# Conn_pcb3.net
KiCad netlist of a schematic drawn in EAGLE
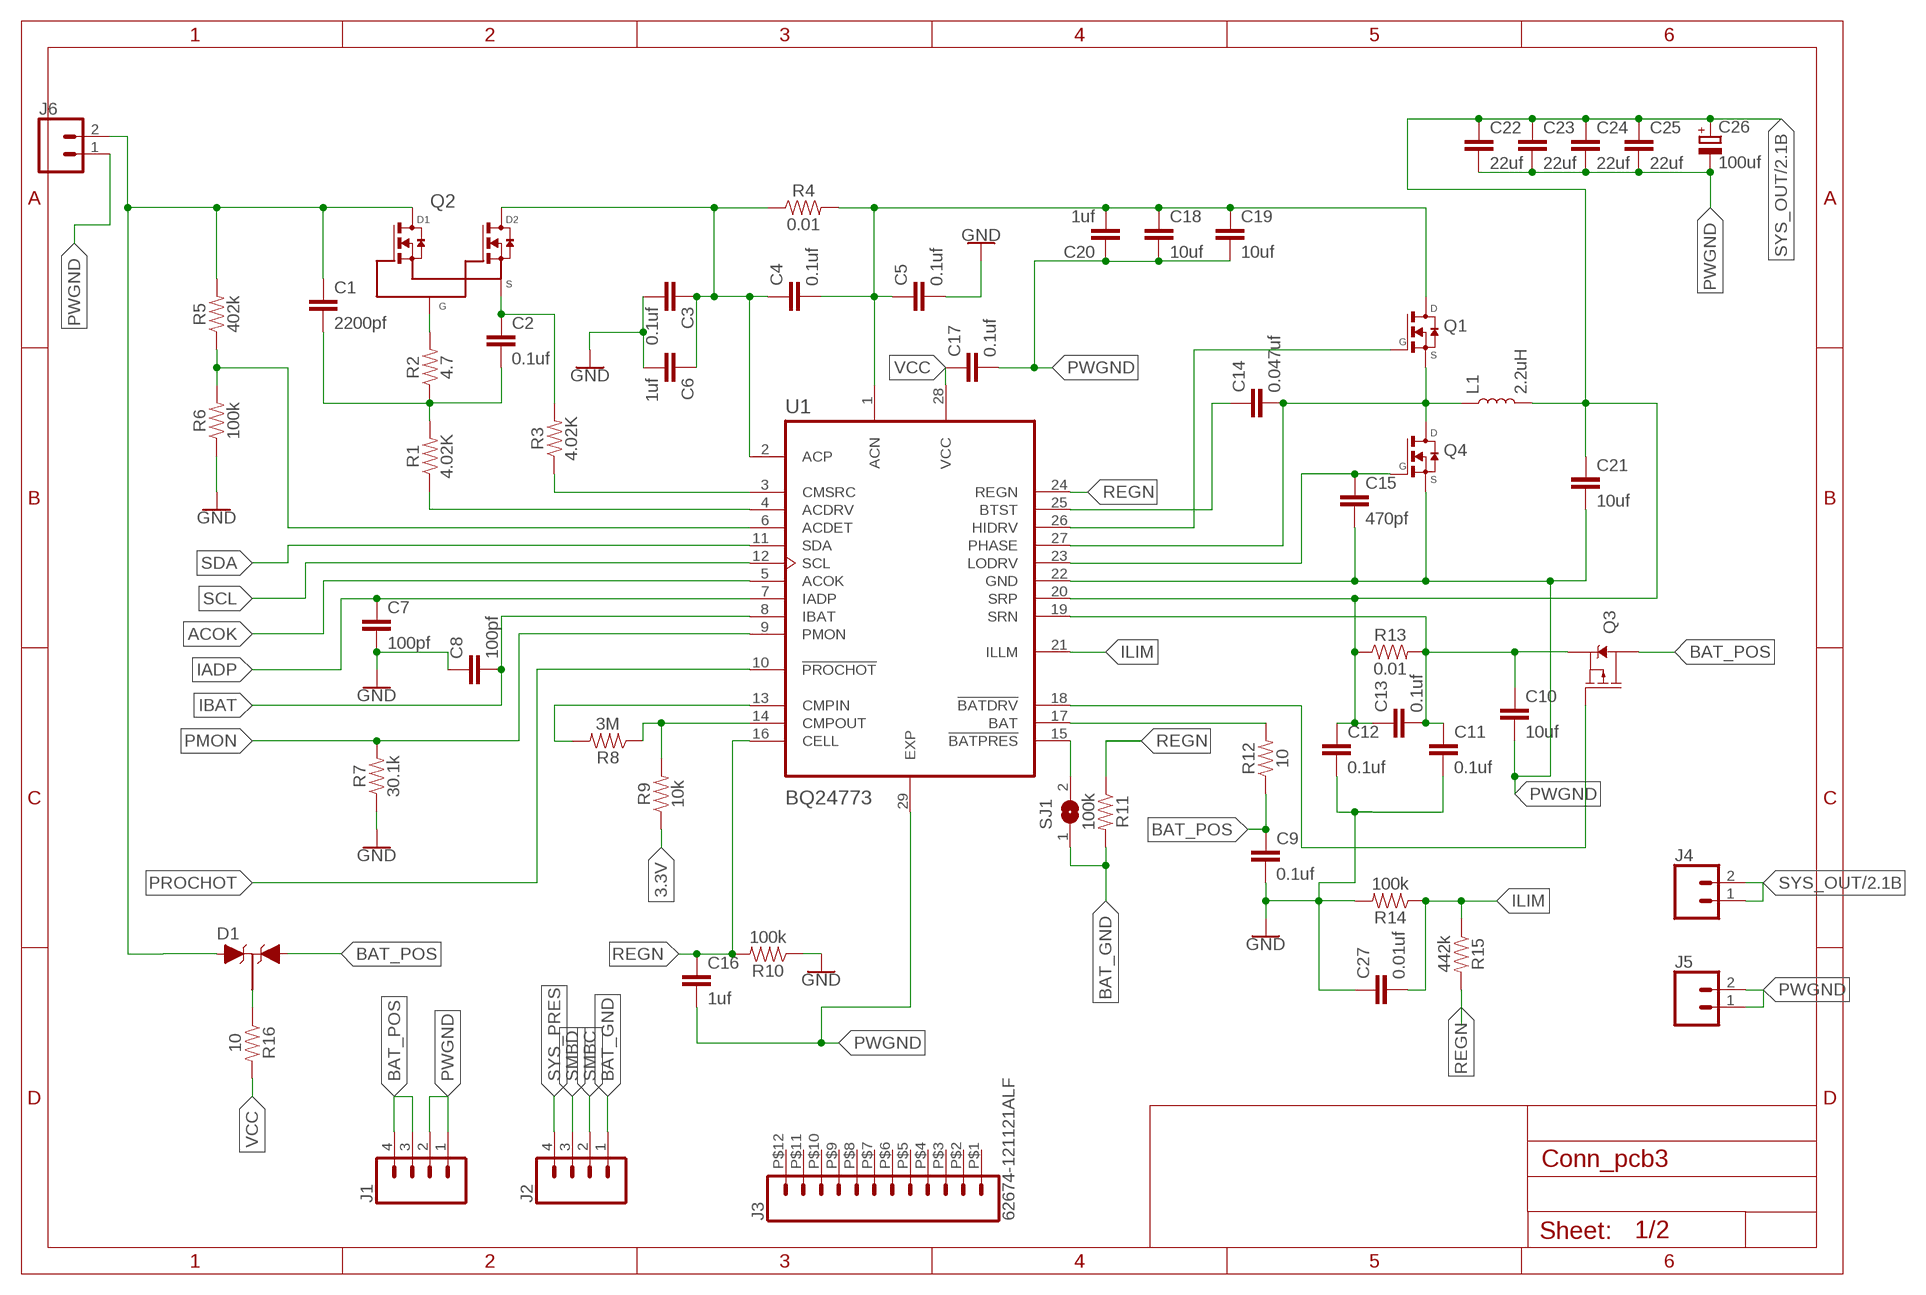
[diagram p0: schematic, sheet 1]
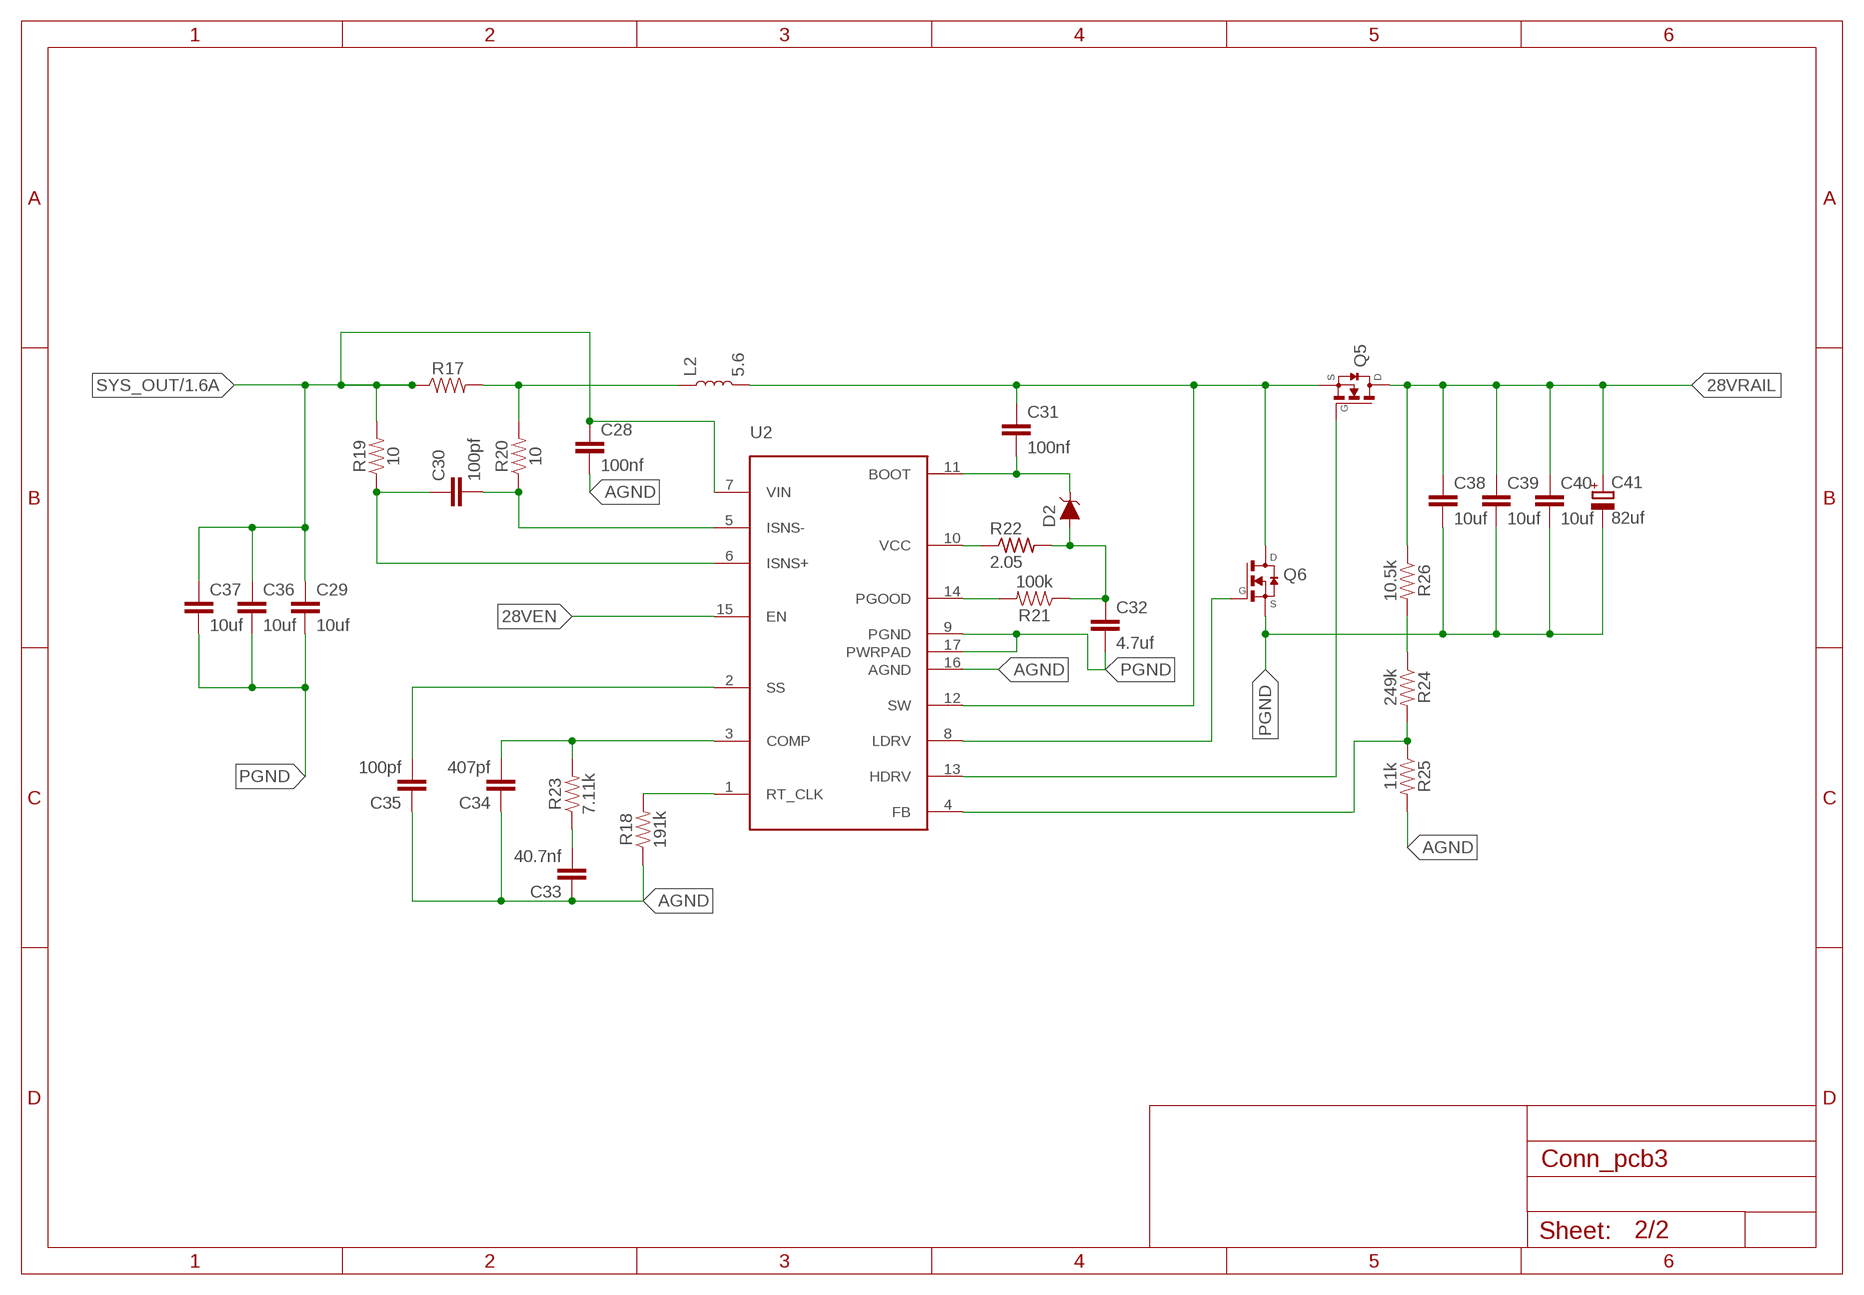
[diagram p1: schematic, sheet 2]

(export (version "E")
  (design (tool "Eeschema 10.0.6"))
  (components
    (comp (ref "C1")
      (value "2200pf")
      (footprint "eagle-import:CAPC1005X50")
      (libsource (lib "eagle-import") (part "CAP0402"))
    )
    (comp (ref "C2")
      (value "0.1uf")
      (footprint "eagle-import:CAPC1005X50")
      (libsource (lib "eagle-import") (part "CAP0402"))
    )
    (comp (ref "C3")
      (value "0.1uf")
      (footprint "eagle-import:CAPC1005X50")
      (libsource (lib "eagle-import") (part "CAP0402"))
    )
    (comp (ref "C4")
      (value "0.1uf")
      (footprint "eagle-import:CAPC1005X50")
      (libsource (lib "eagle-import") (part "CAP0402"))
    )
    (comp (ref "C5")
      (value "0.1uf")
      (footprint "eagle-import:CAPC1005X50")
      (libsource (lib "eagle-import") (part "CAP0402"))
    )
    (comp (ref "C6")
      (value "1uf")
      (footprint "eagle-import:CAPC1005X50")
      (libsource (lib "eagle-import") (part "CAP0402"))
    )
    (comp (ref "C7")
      (value "100pf")
      (footprint "eagle-import:CAPC1005X50")
      (libsource (lib "eagle-import") (part "CAP0402"))
    )
    (comp (ref "C8")
      (value "100pf")
      (footprint "eagle-import:CAPC1005X50")
      (libsource (lib "eagle-import") (part "CAP0402"))
    )
    (comp (ref "C9")
      (value "0.1uf")
      (footprint "eagle-import:CAPC1005X50")
      (libsource (lib "eagle-import") (part "CAP0402"))
    )
    (comp (ref "C10")
      (value "10uf")
      (footprint "eagle-import:C0805K")
      (libsource (lib "eagle-import") (part "C-EUC0805K"))
    )
    (comp (ref "C11")
      (value "0.1uf")
      (footprint "eagle-import:CAPC1005X50")
      (libsource (lib "eagle-import") (part "CAP0402"))
    )
    (comp (ref "C12")
      (value "0.1uf")
      (footprint "eagle-import:CAPC1005X50")
      (libsource (lib "eagle-import") (part "CAP0402"))
    )
    (comp (ref "C13")
      (value "0.1uf")
      (footprint "eagle-import:CAPC1005X50")
      (libsource (lib "eagle-import") (part "CAP0402"))
    )
    (comp (ref "C14")
      (value "0.047uf")
      (footprint "eagle-import:CAPC1005X50")
      (libsource (lib "eagle-import") (part "CAP0402"))
    )
    (comp (ref "C15")
      (value "470pf")
      (footprint "eagle-import:CAPC1005X50")
      (libsource (lib "eagle-import") (part "CAP0402"))
    )
    (comp (ref "C16")
      (value "1uf")
      (footprint "eagle-import:CAPC1005X50")
      (libsource (lib "eagle-import") (part "CAP0402"))
    )
    (comp (ref "C17")
      (value "0.1uf")
      (footprint "eagle-import:CAPC1005X50")
      (libsource (lib "eagle-import") (part "CAP0402"))
    )
    (comp (ref "C18")
      (value "10uf")
      (footprint "eagle-import:C0805K")
      (libsource (lib "eagle-import") (part "C-EUC0805K"))
    )
    (comp (ref "C19")
      (value "10uf")
      (footprint "eagle-import:C0805K")
      (libsource (lib "eagle-import") (part "C-EUC0805K"))
    )
    (comp (ref "C20")
      (value "1uf")
      (footprint "eagle-import:CAPC1005X50")
      (libsource (lib "eagle-import") (part "CAP0402"))
    )
    (comp (ref "C21")
      (value "10uf")
      (footprint "eagle-import:C0805K")
      (libsource (lib "eagle-import") (part "C-EUC0805K"))
    )
    (comp (ref "C22")
      (value "22uf")
      (footprint "eagle-import:C1206")
      (libsource (lib "eagle-import") (part "C-EUC1206"))
    )
    (comp (ref "C23")
      (value "22uf")
      (footprint "eagle-import:C1206")
      (libsource (lib "eagle-import") (part "C-EUC1206"))
    )
    (comp (ref "C24")
      (value "22uf")
      (footprint "eagle-import:C1206")
      (libsource (lib "eagle-import") (part "C-EUC1206"))
    )
    (comp (ref "C25")
      (value "22uf")
      (footprint "eagle-import:C1206")
      (libsource (lib "eagle-import") (part "C-EUC1206"))
    )
    (comp (ref "C26")
      (value "100uf")
      (footprint "eagle-import:CAPAE1030X800")
      (libsource (lib "eagle-import") (part "16SVP100M"))
    )
    (comp (ref "C27")
      (value "0.01uf")
      (footprint "eagle-import:CAPC1005X50")
      (libsource (lib "eagle-import") (part "CAP0402"))
    )
    (comp (ref "D1")
      (value "BAT54C-7-F")
      (footprint "eagle-import:SOT95P235X110-3")
      (libsource (lib "eagle-import") (part "BAT54C-7-F"))
    )
    (comp (ref "J1")
      (value "CONN_041.3")
      (footprint "eagle-import:1X04_NO_SILK_1.3")
      (libsource (lib "eagle-import") (part "CONN_041.3"))
    )
    (comp (ref "J2")
      (value "CONN_041.3")
      (footprint "eagle-import:1X04_NO_SILK_1.3")
      (libsource (lib "eagle-import") (part "CONN_041.3"))
    )
    (comp (ref "J3")
      (value "62674-121121ALF")
      (footprint "eagle-import:62674-121121ALF")
      (libsource (lib "eagle-import") (part "62674-121121ALF"))
    )
    (comp (ref "J4")
      (value "CONN_021.4HOLE")
      (footprint "eagle-import:1X02_1.4HOLE")
      (libsource (lib "eagle-import") (part "CONN_021.4HOLE"))
    )
    (comp (ref "J5")
      (value "CONN_021.4HOLE")
      (footprint "eagle-import:1X02_1.4HOLE")
      (libsource (lib "eagle-import") (part "CONN_021.4HOLE"))
    )
    (comp (ref "J6")
      (value "CONN_021.4HOLE")
      (footprint "eagle-import:1X02_1.4HOLE")
      (libsource (lib "eagle-import") (part "CONN_021.4HOLE"))
    )
    (comp (ref "L1")
      (value "2.2uH")
      (footprint "eagle-import:RESM6365X610")
      (libsource (lib "eagle-import") (part "XEL6060-222MEB"))
    )
    (comp (ref "Q1")
      (value "CSD17308Q3")
      (footprint "eagle-import:SON65P330X330X110-8")
      (fields (field (name "SPICEPREFIX") "Q"))
      (libsource (lib "eagle-import") (part "CSD17308Q3"))
    )
    (comp (ref "Q2")
      (value "CSD87312Q3EVSON")
      (footprint "eagle-import:QFN65P330X330X100-12")
      (libsource (lib "eagle-import") (part "CSD87312Q3EVSON"))
    )
    (comp (ref "Q3")
      (value "CSD25402Q3A")
      (footprint "eagle-import:CSD25402Q3A")
      (libsource (lib "eagle-import") (part "CSD25402Q3A"))
    )
    (comp (ref "Q4")
      (value "CSD17308Q3")
      (footprint "eagle-import:SON65P330X330X110-8")
      (fields (field (name "SPICEPREFIX") "Q"))
      (libsource (lib "eagle-import") (part "CSD17308Q3"))
    )
    (comp (ref "R1")
      (value "4.02K")
      (footprint "eagle-import:0402")
      (libsource (lib "eagle-import") (part "RES4K04020402"))
    )
    (comp (ref "R2")
      (value "4.7")
      (footprint "eagle-import:0402")
      (libsource (lib "eagle-import") (part "RES4K04020402"))
    )
    (comp (ref "R3")
      (value "4.02K")
      (footprint "eagle-import:0402")
      (libsource (lib "eagle-import") (part "RES4K04020402"))
    )
    (comp (ref "R4")
      (value "0.01")
      (footprint "eagle-import:1206")
      (libsource (lib "eagle-import") (part "SENSE-RES"))
    )
    (comp (ref "R5")
      (value "402k")
      (footprint "eagle-import:0402")
      (libsource (lib "eagle-import") (part "RES4K04020402"))
    )
    (comp (ref "R6")
      (value "100k")
      (footprint "eagle-import:0402")
      (libsource (lib "eagle-import") (part "RES4K04020402"))
    )
    (comp (ref "R7")
      (value "30.1k")
      (footprint "eagle-import:0402")
      (libsource (lib "eagle-import") (part "RES4K04020402"))
    )
    (comp (ref "R8")
      (value "3M")
      (footprint "eagle-import:0402")
      (libsource (lib "eagle-import") (part "RES4K04020402"))
    )
    (comp (ref "R9")
      (value "10k")
      (footprint "eagle-import:0402")
      (libsource (lib "eagle-import") (part "RES4K04020402"))
    )
    (comp (ref "R10")
      (value "100k")
      (footprint "eagle-import:0402")
      (libsource (lib "eagle-import") (part "RES4K04020402"))
    )
    (comp (ref "R11")
      (value "100k")
      (footprint "eagle-import:0402")
      (libsource (lib "eagle-import") (part "RES4K04020402"))
    )
    (comp (ref "R12")
      (value "10")
      (footprint "eagle-import:0402")
      (libsource (lib "eagle-import") (part "RES4K04020402"))
    )
    (comp (ref "R13")
      (value "0.01")
      (footprint "eagle-import:1206")
      (libsource (lib "eagle-import") (part "SENSE-RES"))
    )
    (comp (ref "R14")
      (value "100k")
      (footprint "eagle-import:0402")
      (libsource (lib "eagle-import") (part "RES4K04020402"))
    )
    (comp (ref "R15")
      (value "442k")
      (footprint "eagle-import:0402")
      (libsource (lib "eagle-import") (part "RES4K04020402"))
    )
    (comp (ref "R16")
      (value "10")
      (footprint "eagle-import:0402")
      (libsource (lib "eagle-import") (part "RES4K04020402"))
    )
    (comp (ref "SJ1") (value "SJ") (footprint "eagle-import:SJ") (libsource (lib "eagle-import") (part "SJ")))
    (comp (ref "U1")
      (value "BQ24773")
      (footprint "eagle-import:QFN40P400X400X80-29T240")
      (libsource (lib "eagle-import") (part "BQ24773"))
    )
    (comp (ref "C28")
      (value "100nf")
      (footprint "eagle-import:C0402K")
      (libsource (lib "eagle-import") (part "C-EUC0402K"))
    )
    (comp (ref "C29")
      (value "10uf")
      (footprint "eagle-import:C0805K")
      (libsource (lib "eagle-import") (part "C-EUC0805K"))
    )
    (comp (ref "C30")
      (value "100pf")
      (footprint "eagle-import:C0402K")
      (libsource (lib "eagle-import") (part "C-EUC0402K"))
    )
    (comp (ref "C31")
      (value "100nf")
      (footprint "eagle-import:C0402K")
      (libsource (lib "eagle-import") (part "C-EUC0402K"))
    )
    (comp (ref "C32")
      (value "4.7uf")
      (footprint "eagle-import:C0402K")
      (libsource (lib "eagle-import") (part "C-EUC0402K"))
    )
    (comp (ref "C33")
      (value "40.7nf")
      (footprint "eagle-import:C0402K")
      (libsource (lib "eagle-import") (part "C-EUC0402K"))
    )
    (comp (ref "C34")
      (value "407pf")
      (footprint "eagle-import:C0402K")
      (libsource (lib "eagle-import") (part "C-EUC0402K"))
    )
    (comp (ref "C35")
      (value "100pf")
      (footprint "eagle-import:C0402K")
      (libsource (lib "eagle-import") (part "C-EUC0402K"))
    )
    (comp (ref "C36")
      (value "10uf")
      (footprint "eagle-import:C0805K")
      (libsource (lib "eagle-import") (part "C-EUC0805K"))
    )
    (comp (ref "C37")
      (value "10uf")
      (footprint "eagle-import:C0805K")
      (libsource (lib "eagle-import") (part "C-EUC0805K"))
    )
    (comp (ref "C38")
      (value "10uf")
      (footprint "eagle-import:C0805K")
      (libsource (lib "eagle-import") (part "C-EUC0805K"))
    )
    (comp (ref "C39")
      (value "10uf")
      (footprint "eagle-import:C0805K")
      (libsource (lib "eagle-import") (part "C-EUC0805K"))
    )
    (comp (ref "C40")
      (value "10uf")
      (footprint "eagle-import:C0805K")
      (libsource (lib "eagle-import") (part "C-EUC0805K"))
    )
    (comp (ref "C41")
      (value "82uf")
      (footprint "eagle-import:CAPAE830X1040")
      (libsource (lib "eagle-import") (part "PCR1H820MCL6GS"))
    )
    (comp (ref "D2")
      (value "SS24FL")
      (footprint "eagle-import:SODFL3617X108")
      (libsource (lib "eagle-import") (part "SS24FL"))
    )
    (comp (ref "L2")
      (value "5.6")
      (footprint "eagle-import:RESM7275X700")
      (libsource (lib "eagle-import") (part "XAL7070-472MEB"))
    )
    (comp (ref "Q5")
      (value "SIS184DN-T1-GE3")
      (footprint "eagle-import:SIS184DN-T1-GE3")
      (libsource (lib "eagle-import") (part "SIS184DN-T1-GE3"))
    )
    (comp (ref "Q6")
      (value "SIS184DN-T1-GE3")
      (footprint "eagle-import:SIS184DN-T1-GE3")
      (libsource (lib "eagle-import") (part "SIS184DN-T1-GE3"))
    )
    (comp (ref "R17")
      (value "LRMAM2512-R0035FT4")
      (footprint "eagle-import:RESC6432X90")
      (libsource (lib "eagle-import") (part "LRMAM2512-R0035FT4"))
    )
    (comp (ref "R18")
      (value "191k")
      (footprint "eagle-import:0402")
      (libsource (lib "eagle-import") (part "RES4K04020402"))
    )
    (comp (ref "R19")
      (value "10")
      (footprint "eagle-import:0402")
      (libsource (lib "eagle-import") (part "RES4K04020402"))
    )
    (comp (ref "R20")
      (value "10")
      (footprint "eagle-import:0402")
      (libsource (lib "eagle-import") (part "RES4K04020402"))
    )
    (comp (ref "R21")
      (value "100k")
      (footprint "eagle-import:0402")
      (libsource (lib "eagle-import") (part "RES4K04020402"))
    )
    (comp (ref "R22")
      (value "2.05")
      (footprint "eagle-import:R0603")
      (libsource (lib "eagle-import") (part "R-US_R0603"))
    )
    (comp (ref "R23")
      (value "7.11k")
      (footprint "eagle-import:0402")
      (libsource (lib "eagle-import") (part "RES4K04020402"))
    )
    (comp (ref "R24")
      (value "249k")
      (footprint "eagle-import:0402")
      (libsource (lib "eagle-import") (part "RES4K04020402"))
    )
    (comp (ref "R25")
      (value "11k")
      (footprint "eagle-import:0402")
      (libsource (lib "eagle-import") (part "RES4K04020402"))
    )
    (comp (ref "R26")
      (value "10.5k")
      (footprint "eagle-import:0402")
      (libsource (lib "eagle-import") (part "RES4K04020402"))
    )
    (comp (ref "U2")
      (value "TPS43061")
      (footprint "eagle-import:QFN50P300X300X100-17T80X120")
      (libsource (lib "eagle-import") (part "TPS43061"))
    )
  )
  (nets
    (net (code "1") (name "3.3V") (class "Default")
      (node (ref "R9") (pin "1") (pinfunction "1_1") (pintype "passive"))
    )
    (net (code "2") (name "28VEN") (class "Default")
      (node (ref "U2") (pin "15") (pinfunction "EN_15") (pintype "bidirectional"))
    )
    (net (code "3") (name "28VRAIL") (class "Default")
      (node (ref "C38") (pin "1") (pinfunction "1_1") (pintype "passive"))
      (node (ref "C39") (pin "1") (pinfunction "1_1") (pintype "passive"))
      (node (ref "C40") (pin "1") (pinfunction "1_1") (pintype "passive"))
      (node (ref "C41") (pin "1") (pinfunction "+_1") (pintype "passive"))
      (node (ref "Q5") (pin "P$5") (pinfunction "D_P$5") (pintype "passive"))
      (node (ref "Q5") (pin "P$6") (pinfunction "D_P$6") (pintype "passive"))
      (node (ref "Q5") (pin "P$7") (pinfunction "D_P$7") (pintype "passive"))
      (node (ref "Q5") (pin "P$8") (pinfunction "D_P$8") (pintype "passive"))
      (node (ref "Q5") (pin "P$9") (pinfunction "D_P$9") (pintype "passive"))
      (node (ref "R26") (pin "1") (pinfunction "1_1") (pintype "passive"))
    )
    (net (code "4") (name "ACOK") (class "Default")
      (node (ref "U1") (pin "5") (pinfunction "ACOK_5") (pintype "output"))
    )
    (net (code "5") (name "AGND") (class "Default")
      (node (ref "C28") (pin "2") (pinfunction "2_2") (pintype "passive"))
      (node (ref "C33") (pin "1") (pinfunction "1_1") (pintype "passive"))
      (node (ref "C34") (pin "1") (pinfunction "1_1") (pintype "passive"))
      (node (ref "C35") (pin "1") (pinfunction "1_1") (pintype "passive"))
      (node (ref "R18") (pin "1") (pinfunction "1_1") (pintype "passive"))
      (node (ref "R25") (pin "2") (pinfunction "2_2") (pintype "passive"))
      (node (ref "U2") (pin "16") (pinfunction "AGND_16") (pintype "bidirectional"))
    )
    (net (code "6") (name "BAT_GND") (class "Default")
      (node (ref "J2") (pin "1") (pinfunction "1_1") (pintype "passive"))
      (node (ref "R11") (pin "2") (pinfunction "2_2") (pintype "passive"))
      (node (ref "SJ1") (pin "1") (pinfunction "1_1") (pintype "passive"))
    )
    (net (code "7") (name "BAT_POS") (class "Default")
      (node (ref "C9") (pin "1") (pinfunction "1_1") (pintype "passive"))
      (node (ref "D1") (pin "2") (pinfunction "A2_2") (pintype "passive"))
      (node (ref "J1") (pin "3") (pinfunction "3_3") (pintype "passive"))
      (node (ref "J1") (pin "4") (pinfunction "4_4") (pintype "passive"))
      (node (ref "Q3") (pin "1") (pinfunction "D_1") (pintype "bidirectional"))
      (node (ref "Q3") (pin "2") (pinfunction "D_2") (pintype "bidirectional"))
      (node (ref "Q3") (pin "3") (pinfunction "D_3") (pintype "bidirectional"))
      (node (ref "R12") (pin "1") (pinfunction "1_1") (pintype "passive"))
    )
    (net (code "8") (name "GND") (class "Default")
      (node (ref "C11") (pin "2") (pinfunction "2_2") (pintype "passive"))
      (node (ref "C12") (pin "2") (pinfunction "2_2") (pintype "passive"))
      (node (ref "C27") (pin "1") (pinfunction "1_1") (pintype "passive"))
      (node (ref "C3") (pin "2") (pinfunction "2_2") (pintype "passive"))
      (node (ref "C5") (pin "2") (pinfunction "2_2") (pintype "passive"))
      (node (ref "C6") (pin "2") (pinfunction "2_2") (pintype "passive"))
      (node (ref "C7") (pin "2") (pinfunction "2_2") (pintype "passive"))
      (node (ref "C8") (pin "1") (pinfunction "1_1") (pintype "passive"))
      (node (ref "C9") (pin "2") (pinfunction "2_2") (pintype "passive"))
      (node (ref "R10") (pin "1") (pinfunction "1_1") (pintype "passive"))
      (node (ref "R14") (pin "2") (pinfunction "2_2") (pintype "passive"))
      (node (ref "R6") (pin "1") (pinfunction "1_1") (pintype "passive"))
      (node (ref "R7") (pin "1") (pinfunction "1_1") (pintype "passive"))
    )
    (net (code "9") (name "IADP") (class "Default")
      (node (ref "C7") (pin "1") (pinfunction "1_1") (pintype "passive"))
      (node (ref "U1") (pin "7") (pinfunction "IADP_7") (pintype "output"))
    )
    (net (code "10") (name "IBAT") (class "Default")
      (node (ref "C8") (pin "2") (pinfunction "2_2") (pintype "passive"))
      (node (ref "U1") (pin "8") (pinfunction "IBAT_8") (pintype "output"))
    )
    (net (code "11") (name "ILIM") (class "Default")
      (node (ref "C27") (pin "2") (pinfunction "2_2") (pintype "passive"))
      (node (ref "R14") (pin "1") (pinfunction "1_1") (pintype "passive"))
      (node (ref "R15") (pin "1") (pinfunction "1_1") (pintype "passive"))
      (node (ref "U1") (pin "21") (pinfunction "ILLM_21") (pintype "input"))
    )
    (net (code "12") (name "Net-(C1-Pad2)") (class "Default")
      (node (ref "C1") (pin "2") (pinfunction "2_2") (pintype "passive"))
      (node (ref "C2") (pin "2") (pinfunction "2_2") (pintype "passive"))
      (node (ref "R1") (pin "2") (pinfunction "2_2") (pintype "passive"))
      (node (ref "R2") (pin "1") (pinfunction "1_1") (pintype "passive"))
    )
    (net (code "13") (name "Net-(C2-Pad1)") (class "Default")
      (node (ref "C2") (pin "1") (pinfunction "1_1") (pintype "passive"))
      (node (ref "Q2") (pin "9") (pinfunction "S_9") (pintype "passive"))
      (node (ref "Q2") (pin "9.1") (pinfunction "S_9.1") (pintype "passive"))
      (node (ref "Q2") (pin "9.2") (pinfunction "S_9.2") (pintype "passive"))
      (node (ref "Q2") (pin "9.3") (pinfunction "S_9.3") (pintype "passive"))
      (node (ref "Q2") (pin "9.4") (pinfunction "S_9.4") (pintype "passive"))
      (node (ref "R3") (pin "2") (pinfunction "2_2") (pintype "passive"))
    )
    (net (code "14") (name "Net-(C33-Pad2)") (class "Default")
      (node (ref "C33") (pin "2") (pinfunction "2_2") (pintype "passive"))
      (node (ref "R23") (pin "1") (pinfunction "1_1") (pintype "passive"))
    )
    (net (code "15") (name "Net-(D1-A1)") (class "Default")
      (node (ref "C1") (pin "1") (pinfunction "1_1") (pintype "passive"))
      (node (ref "D1") (pin "1") (pinfunction "A1_1") (pintype "passive"))
      (node (ref "J6") (pin "2") (pinfunction "2_2") (pintype "passive"))
      (node (ref "Q2") (pin "1") (pinfunction "D1_1") (pintype "passive"))
      (node (ref "Q2") (pin "3") (pinfunction "D1_3") (pintype "passive"))
      (node (ref "Q2") (pin "4") (pinfunction "D1_4") (pintype "passive"))
      (node (ref "R5") (pin "2") (pinfunction "2_2") (pintype "passive"))
    )
    (net (code "16") (name "Net-(D1-K)") (class "Default")
      (node (ref "D1") (pin "3") (pinfunction "K_3") (pintype "passive"))
      (node (ref "R16") (pin "1") (pinfunction "1_1") (pintype "passive"))
    )
    (net (code "17") (name "Net-(D2-A)") (class "Default")
      (node (ref "C32") (pin "1") (pinfunction "1_1") (pintype "passive"))
      (node (ref "D2") (pin "2") (pinfunction "A_2") (pintype "passive"))
      (node (ref "R21") (pin "1") (pinfunction "1_1") (pintype "passive"))
      (node (ref "R22") (pin "2") (pinfunction "2_2") (pintype "passive"))
    )
    (net (code "18") (name "Net-(D2-C)") (class "Default")
      (node (ref "C31") (pin "2") (pinfunction "2_2") (pintype "passive"))
      (node (ref "D2") (pin "1") (pinfunction "C_1") (pintype "passive"))
      (node (ref "U2") (pin "11") (pinfunction "BOOT_11") (pintype "bidirectional"))
    )
    (net (code "19") (name "Net-(L2-Pad1)") (class "Default")
      (node (ref "L2") (pin "1") (pinfunction "1_1") (pintype "passive"))
      (node (ref "R17") (pin "2") (pinfunction "2_2") (pintype "passive"))
      (node (ref "R20") (pin "2") (pinfunction "2_2") (pintype "passive"))
    )
    (net (code "20") (name "Net-(Q1-G)") (class "Default")
      (node (ref "Q1") (pin "4") (pinfunction "G_4") (pintype "passive"))
      (node (ref "U1") (pin "26") (pinfunction "HIDRV_26") (pintype "output"))
    )
    (net (code "21") (name "Net-(Q2-G)") (class "Default")
      (node (ref "Q2") (pin "5") (pinfunction "G_5") (pintype "passive"))
      (node (ref "R2") (pin "2") (pinfunction "2_2") (pintype "passive"))
    )
    (net (code "22") (name "Net-(Q3-G)") (class "Default")
      (node (ref "Q3") (pin "4") (pinfunction "G_4") (pintype "bidirectional"))
      (node (ref "U1") (pin "18") (pinfunction "~{BATDRV}_18") (pintype "output"))
    )
    (net (code "23") (name "Net-(Q4-G)") (class "Default")
      (node (ref "C15") (pin "1") (pinfunction "1_1") (pintype "passive"))
      (node (ref "Q4") (pin "4") (pinfunction "G_4") (pintype "passive"))
      (node (ref "U1") (pin "23") (pinfunction "LODRV_23") (pintype "output"))
    )
    (net (code "24") (name "Net-(Q5-G)") (class "Default")
      (node (ref "Q5") (pin "P$4") (pinfunction "G_P$4") (pintype "passive"))
      (node (ref "U2") (pin "13") (pinfunction "HDRV_13") (pintype "bidirectional"))
    )
    (net (code "25") (name "Net-(Q6-G)") (class "Default")
      (node (ref "Q6") (pin "P$4") (pinfunction "G_P$4") (pintype "passive"))
      (node (ref "U2") (pin "8") (pinfunction "LDRV_8") (pintype "bidirectional"))
    )
    (net (code "26") (name "Net-(R24-Pad1)") (class "Default")
      (node (ref "R24") (pin "1") (pinfunction "1_1") (pintype "passive"))
      (node (ref "R26") (pin "2") (pinfunction "2_2") (pintype "passive"))
    )
    (net (code "27") (name "Net-(U1-ACDET)") (class "Default")
      (node (ref "R5") (pin "1") (pinfunction "1_1") (pintype "passive"))
      (node (ref "R6") (pin "2") (pinfunction "2_2") (pintype "passive"))
      (node (ref "U1") (pin "6") (pinfunction "ACDET_6") (pintype "input"))
    )
    (net (code "28") (name "Net-(U1-ACDRV)") (class "Default")
      (node (ref "R1") (pin "1") (pinfunction "1_1") (pintype "passive"))
      (node (ref "U1") (pin "4") (pinfunction "ACDRV_4") (pintype "output"))
    )
    (net (code "29") (name "Net-(U1-ACN)") (class "Default")
      (node (ref "C18") (pin "1") (pinfunction "1_1") (pintype "passive"))
      (node (ref "C19") (pin "1") (pinfunction "1_1") (pintype "passive"))
      (node (ref "C20") (pin "2") (pinfunction "2_2") (pintype "passive"))
      (node (ref "C4") (pin "2") (pinfunction "2_2") (pintype "passive"))
      (node (ref "C5") (pin "1") (pinfunction "1_1") (pintype "passive"))
      (node (ref "Q1") (pin "5") (pinfunction "D_5") (pintype "passive"))
      (node (ref "Q1") (pin "6") (pinfunction "D_6") (pintype "passive"))
      (node (ref "Q1") (pin "7") (pinfunction "D_7") (pintype "passive"))
      (node (ref "Q1") (pin "8") (pinfunction "D_8") (pintype "passive"))
      (node (ref "R4") (pin "2") (pinfunction "2_2") (pintype "passive"))
      (node (ref "U1") (pin "1") (pinfunction "ACN_1") (pintype "input"))
    )
    (net (code "30") (name "Net-(U1-ACP)") (class "Default")
      (node (ref "C3") (pin "1") (pinfunction "1_1") (pintype "passive"))
      (node (ref "C4") (pin "1") (pinfunction "1_1") (pintype "passive"))
      (node (ref "C6") (pin "1") (pinfunction "1_1") (pintype "passive"))
      (node (ref "Q2") (pin "6") (pinfunction "D2_6") (pintype "passive"))
      (node (ref "Q2") (pin "7") (pinfunction "D2_7") (pintype "passive"))
      (node (ref "Q2") (pin "8") (pinfunction "D2_8") (pintype "passive"))
      (node (ref "R4") (pin "1") (pinfunction "1_1") (pintype "passive"))
      (node (ref "U1") (pin "2") (pinfunction "ACP_2") (pintype "input"))
    )
    (net (code "31") (name "Net-(U1-BAT)") (class "Default")
      (node (ref "R12") (pin "2") (pinfunction "2_2") (pintype "passive"))
      (node (ref "U1") (pin "17") (pinfunction "BAT_17") (pintype "input"))
    )
    (net (code "32") (name "Net-(U1-BTST)") (class "Default")
      (node (ref "C14") (pin "1") (pinfunction "1_1") (pintype "passive"))
      (node (ref "U1") (pin "25") (pinfunction "BTST_25") (pintype "passive"))
    )
    (net (code "33") (name "Net-(U1-CMPIN)") (class "Default")
      (node (ref "R8") (pin "2") (pinfunction "2_2") (pintype "passive"))
      (node (ref "U1") (pin "13") (pinfunction "CMPIN_13") (pintype "input"))
    )
    (net (code "34") (name "Net-(U1-CMPOUT)") (class "Default")
      (node (ref "R8") (pin "1") (pinfunction "1_1") (pintype "passive"))
      (node (ref "R9") (pin "2") (pinfunction "2_2") (pintype "passive"))
      (node (ref "U1") (pin "14") (pinfunction "CMPOUT_14") (pintype "output"))
    )
    (net (code "35") (name "Net-(U1-CMSRC)") (class "Default")
      (node (ref "R3") (pin "1") (pinfunction "1_1") (pintype "passive"))
      (node (ref "U1") (pin "3") (pinfunction "CMSRC_3") (pintype "input"))
    )
    (net (code "36") (name "Net-(U1-PHASE)") (class "Default")
      (node (ref "C14") (pin "2") (pinfunction "2_2") (pintype "passive"))
      (node (ref "L1") (pin "1") (pinfunction "1_1") (pintype "passive"))
      (node (ref "Q1") (pin "1") (pinfunction "S_1") (pintype "passive"))
      (node (ref "Q1") (pin "2") (pinfunction "S_2") (pintype "passive"))
      (node (ref "Q1") (pin "3") (pinfunction "S_3") (pintype "passive"))
      (node (ref "Q4") (pin "5") (pinfunction "D_5") (pintype "passive"))
      (node (ref "Q4") (pin "6") (pinfunction "D_6") (pintype "passive"))
      (node (ref "Q4") (pin "7") (pinfunction "D_7") (pintype "passive"))
      (node (ref "Q4") (pin "8") (pinfunction "D_8") (pintype "passive"))
      (node (ref "U1") (pin "27") (pinfunction "PHASE_27") (pintype "output"))
    )
    (net (code "37") (name "Net-(U1-SRN)") (class "Default")
      (node (ref "C10") (pin "1") (pinfunction "1_1") (pintype "passive"))
      (node (ref "C11") (pin "1") (pinfunction "1_1") (pintype "passive"))
      (node (ref "C13") (pin "2") (pinfunction "2_2") (pintype "passive"))
      (node (ref "Q3") (pin "5") (pinfunction "S_5") (pintype "bidirectional"))
      (node (ref "Q3") (pin "6") (pinfunction "S_6") (pintype "bidirectional"))
      (node (ref "Q3") (pin "7") (pinfunction "S_7") (pintype "bidirectional"))
      (node (ref "Q3") (pin "8") (pinfunction "S_8") (pintype "bidirectional"))
      (node (ref "Q3") (pin "9") (pinfunction "S_9") (pintype "bidirectional"))
      (node (ref "R13") (pin "2") (pinfunction "2_2") (pintype "passive"))
      (node (ref "U1") (pin "19") (pinfunction "SRN_19") (pintype "input"))
    )
    (net (code "38") (name "Net-(U1-~{BATPRES})") (class "Default")
      (node (ref "SJ1") (pin "2") (pinfunction "2_2") (pintype "passive"))
      (node (ref "U1") (pin "15") (pinfunction "~{BATPRES}_15") (pintype "input"))
    )
    (net (code "39") (name "Net-(U2-COMP)") (class "Default")
      (node (ref "C34") (pin "2") (pinfunction "2_2") (pintype "passive"))
      (node (ref "R23") (pin "2") (pinfunction "2_2") (pintype "passive"))
      (node (ref "U2") (pin "3") (pinfunction "COMP_3") (pintype "bidirectional"))
    )
    (net (code "40") (name "Net-(U2-FB)") (class "Default")
      (node (ref "R24") (pin "2") (pinfunction "2_2") (pintype "passive"))
      (node (ref "R25") (pin "1") (pinfunction "1_1") (pintype "passive"))
      (node (ref "U2") (pin "4") (pinfunction "FB_4") (pintype "bidirectional"))
    )
    (net (code "41") (name "Net-(U2-ISNS+)") (class "Default")
      (node (ref "C30") (pin "1") (pinfunction "1_1") (pintype "passive"))
      (node (ref "R19") (pin "1") (pinfunction "1_1") (pintype "passive"))
      (node (ref "U2") (pin "6") (pinfunction "ISNS+_6") (pintype "bidirectional"))
    )
    (net (code "42") (name "Net-(U2-ISNS-)") (class "Default")
      (node (ref "C30") (pin "2") (pinfunction "2_2") (pintype "passive"))
      (node (ref "R20") (pin "1") (pinfunction "1_1") (pintype "passive"))
      (node (ref "U2") (pin "5") (pinfunction "ISNS-_5") (pintype "bidirectional"))
    )
    (net (code "43") (name "Net-(U2-PGOOD)") (class "Default")
      (node (ref "R21") (pin "2") (pinfunction "2_2") (pintype "passive"))
      (node (ref "U2") (pin "14") (pinfunction "PGOOD_14") (pintype "bidirectional"))
    )
    (net (code "44") (name "Net-(U2-RT_CLK)") (class "Default")
      (node (ref "R18") (pin "2") (pinfunction "2_2") (pintype "passive"))
      (node (ref "U2") (pin "1") (pinfunction "RT_CLK_1") (pintype "bidirectional"))
    )
    (net (code "45") (name "Net-(U2-SS)") (class "Default")
      (node (ref "C35") (pin "2") (pinfunction "2_2") (pintype "passive"))
      (node (ref "U2") (pin "2") (pinfunction "SS_2") (pintype "bidirectional"))
    )
    (net (code "46") (name "Net-(U2-SW)") (class "Default")
      (node (ref "C31") (pin "1") (pinfunction "1_1") (pintype "passive"))
      (node (ref "L2") (pin "2") (pinfunction "2_2") (pintype "passive"))
      (node (ref "Q5") (pin "P$1") (pinfunction "S_P$1") (pintype "passive"))
      (node (ref "Q5") (pin "P$2") (pinfunction "S_P$2") (pintype "passive"))
      (node (ref "Q5") (pin "P$3") (pinfunction "S_P$3") (pintype "passive"))
      (node (ref "Q6") (pin "P$5") (pinfunction "D_P$5") (pintype "passive"))
      (node (ref "Q6") (pin "P$6") (pinfunction "D_P$6") (pintype "passive"))
      (node (ref "Q6") (pin "P$7") (pinfunction "D_P$7") (pintype "passive"))
      (node (ref "Q6") (pin "P$8") (pinfunction "D_P$8") (pintype "passive"))
      (node (ref "Q6") (pin "P$9") (pinfunction "D_P$9") (pintype "passive"))
      (node (ref "U2") (pin "12") (pinfunction "SW_12") (pintype "bidirectional"))
    )
    (net (code "47") (name "Net-(U2-VCC)") (class "Default")
      (node (ref "R22") (pin "1") (pinfunction "1_1") (pintype "passive"))
      (node (ref "U2") (pin "10") (pinfunction "VCC_10") (pintype "bidirectional"))
    )
    (net (code "48") (name "PGND") (class "Default")
      (node (ref "C29") (pin "2") (pinfunction "2_2") (pintype "passive"))
      (node (ref "C32") (pin "2") (pinfunction "2_2") (pintype "passive"))
      (node (ref "C36") (pin "2") (pinfunction "2_2") (pintype "passive"))
      (node (ref "C37") (pin "2") (pinfunction "2_2") (pintype "passive"))
      (node (ref "C38") (pin "2") (pinfunction "2_2") (pintype "passive"))
      (node (ref "C39") (pin "2") (pinfunction "2_2") (pintype "passive"))
      (node (ref "C40") (pin "2") (pinfunction "2_2") (pintype "passive"))
      (node (ref "C41") (pin "2") (pinfunction "-_2") (pintype "passive"))
      (node (ref "Q6") (pin "P$1") (pinfunction "S_P$1") (pintype "passive"))
      (node (ref "Q6") (pin "P$2") (pinfunction "S_P$2") (pintype "passive"))
      (node (ref "Q6") (pin "P$3") (pinfunction "S_P$3") (pintype "passive"))
      (node (ref "U2") (pin "17") (pinfunction "PWRPAD_17") (pintype "bidirectional"))
      (node (ref "U2") (pin "9") (pinfunction "PGND_9") (pintype "bidirectional"))
    )
    (net (code "49") (name "PMON") (class "Default")
      (node (ref "R7") (pin "2") (pinfunction "2_2") (pintype "passive"))
      (node (ref "U1") (pin "9") (pinfunction "PMON_9") (pintype "output"))
    )
    (net (code "50") (name "PROCHOT") (class "Default")
      (node (ref "U1") (pin "10") (pinfunction "~{PROCHOT}_10") (pintype "output"))
    )
    (net (code "51") (name "PWGND") (class "Default")
      (node (ref "C10") (pin "2") (pinfunction "2_2") (pintype "passive"))
      (node (ref "C15") (pin "2") (pinfunction "2_2") (pintype "passive"))
      (node (ref "C16") (pin "2") (pinfunction "2_2") (pintype "passive"))
      (node (ref "C17") (pin "2") (pinfunction "2_2") (pintype "passive"))
      (node (ref "C18") (pin "2") (pinfunction "2_2") (pintype "passive"))
      (node (ref "C19") (pin "2") (pinfunction "2_2") (pintype "passive"))
      (node (ref "C20") (pin "1") (pinfunction "1_1") (pintype "passive"))
      (node (ref "C21") (pin "2") (pinfunction "2_2") (pintype "passive"))
      (node (ref "C22") (pin "2") (pinfunction "2_2") (pintype "passive"))
      (node (ref "C23") (pin "2") (pinfunction "2_2") (pintype "passive"))
      (node (ref "C24") (pin "2") (pinfunction "2_2") (pintype "passive"))
      (node (ref "C25") (pin "2") (pinfunction "2_2") (pintype "passive"))
      (node (ref "C26") (pin "2") (pinfunction "-_2") (pintype "passive"))
      (node (ref "J1") (pin "1") (pinfunction "1_1") (pintype "passive"))
      (node (ref "J1") (pin "2") (pinfunction "2_2") (pintype "passive"))
      (node (ref "J5") (pin "1") (pinfunction "1_1") (pintype "passive"))
      (node (ref "J5") (pin "2") (pinfunction "2_2") (pintype "passive"))
      (node (ref "J6") (pin "1") (pinfunction "1_1") (pintype "passive"))
      (node (ref "Q4") (pin "1") (pinfunction "S_1") (pintype "passive"))
      (node (ref "Q4") (pin "2") (pinfunction "S_2") (pintype "passive"))
      (node (ref "Q4") (pin "3") (pinfunction "S_3") (pintype "passive"))
      (node (ref "U1") (pin "22") (pinfunction "GND_22") (pintype "power_in"))
      (node (ref "U1") (pin "29") (pinfunction "EXP_29") (pintype "power_in"))
    )
    (net (code "52") (name "REGN") (class "Default")
      (node (ref "C16") (pin "1") (pinfunction "1_1") (pintype "passive"))
      (node (ref "R10") (pin "2") (pinfunction "2_2") (pintype "passive"))
      (node (ref "R11") (pin "1") (pinfunction "1_1") (pintype "passive"))
      (node (ref "R15") (pin "2") (pinfunction "2_2") (pintype "passive"))
      (node (ref "U1") (pin "16") (pinfunction "CELL_16") (pintype "input"))
      (node (ref "U1") (pin "24") (pinfunction "REGN_24") (pintype "output"))
    )
    (net (code "53") (name "SCL") (class "Default")
      (node (ref "U1") (pin "12") (pinfunction "SCL_12") (pintype "input"))
    )
    (net (code "54") (name "SDA") (class "Default")
      (node (ref "U1") (pin "11") (pinfunction "SDA_11") (pintype "bidirectional"))
    )
    (net (code "55") (name "SMBC") (class "Default")
      (node (ref "J2") (pin "2") (pinfunction "2_2") (pintype "passive"))
    )
    (net (code "56") (name "SMBD") (class "Default")
      (node (ref "J2") (pin "3") (pinfunction "3_3") (pintype "passive"))
    )
    (net (code "57") (name "SYS_OUT") (class "Default")
      (node (ref "C12") (pin "1") (pinfunction "1_1") (pintype "passive"))
      (node (ref "C13") (pin "1") (pinfunction "1_1") (pintype "passive"))
      (node (ref "C21") (pin "1") (pinfunction "1_1") (pintype "passive"))
      (node (ref "C22") (pin "1") (pinfunction "1_1") (pintype "passive"))
      (node (ref "C23") (pin "1") (pinfunction "1_1") (pintype "passive"))
      (node (ref "C24") (pin "1") (pinfunction "1_1") (pintype "passive"))
      (node (ref "C25") (pin "1") (pinfunction "1_1") (pintype "passive"))
      (node (ref "C26") (pin "1") (pinfunction "+_1") (pintype "passive"))
      (node (ref "C28") (pin "1") (pinfunction "1_1") (pintype "passive"))
      (node (ref "C29") (pin "1") (pinfunction "1_1") (pintype "passive"))
      (node (ref "C36") (pin "1") (pinfunction "1_1") (pintype "passive"))
      (node (ref "C37") (pin "1") (pinfunction "1_1") (pintype "passive"))
      (node (ref "J4") (pin "1") (pinfunction "1_1") (pintype "passive"))
      (node (ref "J4") (pin "2") (pinfunction "2_2") (pintype "passive"))
      (node (ref "L1") (pin "2") (pinfunction "2_2") (pintype "passive"))
      (node (ref "R13") (pin "1") (pinfunction "1_1") (pintype "passive"))
      (node (ref "R17") (pin "1") (pinfunction "1_1") (pintype "passive"))
      (node (ref "R19") (pin "2") (pinfunction "2_2") (pintype "passive"))
      (node (ref "U1") (pin "20") (pinfunction "SRP_20") (pintype "input"))
      (node (ref "U2") (pin "7") (pinfunction "VIN_7") (pintype "bidirectional"))
    )
    (net (code "58") (name "SYS_PRES") (class "Default")
      (node (ref "J2") (pin "4") (pinfunction "4_4") (pintype "passive"))
    )
    (net (code "59") (name "VCC") (class "Default")
      (node (ref "C17") (pin "1") (pinfunction "1_1") (pintype "passive"))
      (node (ref "R16") (pin "2") (pinfunction "2_2") (pintype "passive"))
      (node (ref "U1") (pin "28") (pinfunction "VCC_28") (pintype "power_in"))
    )
    (net (code "60") (name "unconnected-(J3-1-PadP$1)") (class "Default")
      (node (ref "J3") (pin "P$1") (pinfunction "1_P$1") (pintype "passive"))
    )
    (net (code "61") (name "unconnected-(J3-2-PadP$2)") (class "Default")
      (node (ref "J3") (pin "P$2") (pinfunction "2_P$2") (pintype "passive"))
    )
    (net (code "62") (name "unconnected-(J3-3-PadP$3)") (class "Default")
      (node (ref "J3") (pin "P$3") (pinfunction "3_P$3") (pintype "passive"))
    )
    (net (code "63") (name "unconnected-(J3-4-PadP$4)") (class "Default")
      (node (ref "J3") (pin "P$4") (pinfunction "4_P$4") (pintype "passive"))
    )
    (net (code "64") (name "unconnected-(J3-5-PadP$5)") (class "Default")
      (node (ref "J3") (pin "P$5") (pinfunction "5_P$5") (pintype "passive"))
    )
    (net (code "65") (name "unconnected-(J3-6-PadP$6)") (class "Default")
      (node (ref "J3") (pin "P$6") (pinfunction "6_P$6") (pintype "passive"))
    )
    (net (code "66") (name "unconnected-(J3-7-PadP$7)") (class "Default")
      (node (ref "J3") (pin "P$7") (pinfunction "7_P$7") (pintype "passive"))
    )
    (net (code "67") (name "unconnected-(J3-8-PadP$8)") (class "Default")
      (node (ref "J3") (pin "P$8") (pinfunction "8_P$8") (pintype "passive"))
    )
    (net (code "68") (name "unconnected-(J3-9-PadP$9)") (class "Default")
      (node (ref "J3") (pin "P$9") (pinfunction "9_P$9") (pintype "passive"))
    )
    (net (code "69") (name "unconnected-(J3-10-PadP$10)") (class "Default")
      (node (ref "J3") (pin "P$10") (pinfunction "10_P$10") (pintype "passive"))
    )
    (net (code "70") (name "unconnected-(J3-11-PadP$11)") (class "Default")
      (node (ref "J3") (pin "P$11") (pinfunction "11_P$11") (pintype "passive"))
    )
    (net (code "71") (name "unconnected-(J3-12-PadP$12)") (class "Default")
      (node (ref "J3") (pin "P$12") (pinfunction "12_P$12") (pintype "passive"))
    )
  )
)
